# Mono_main_board_V3.net
KiCad netlist of a schematic drawn in EAGLE
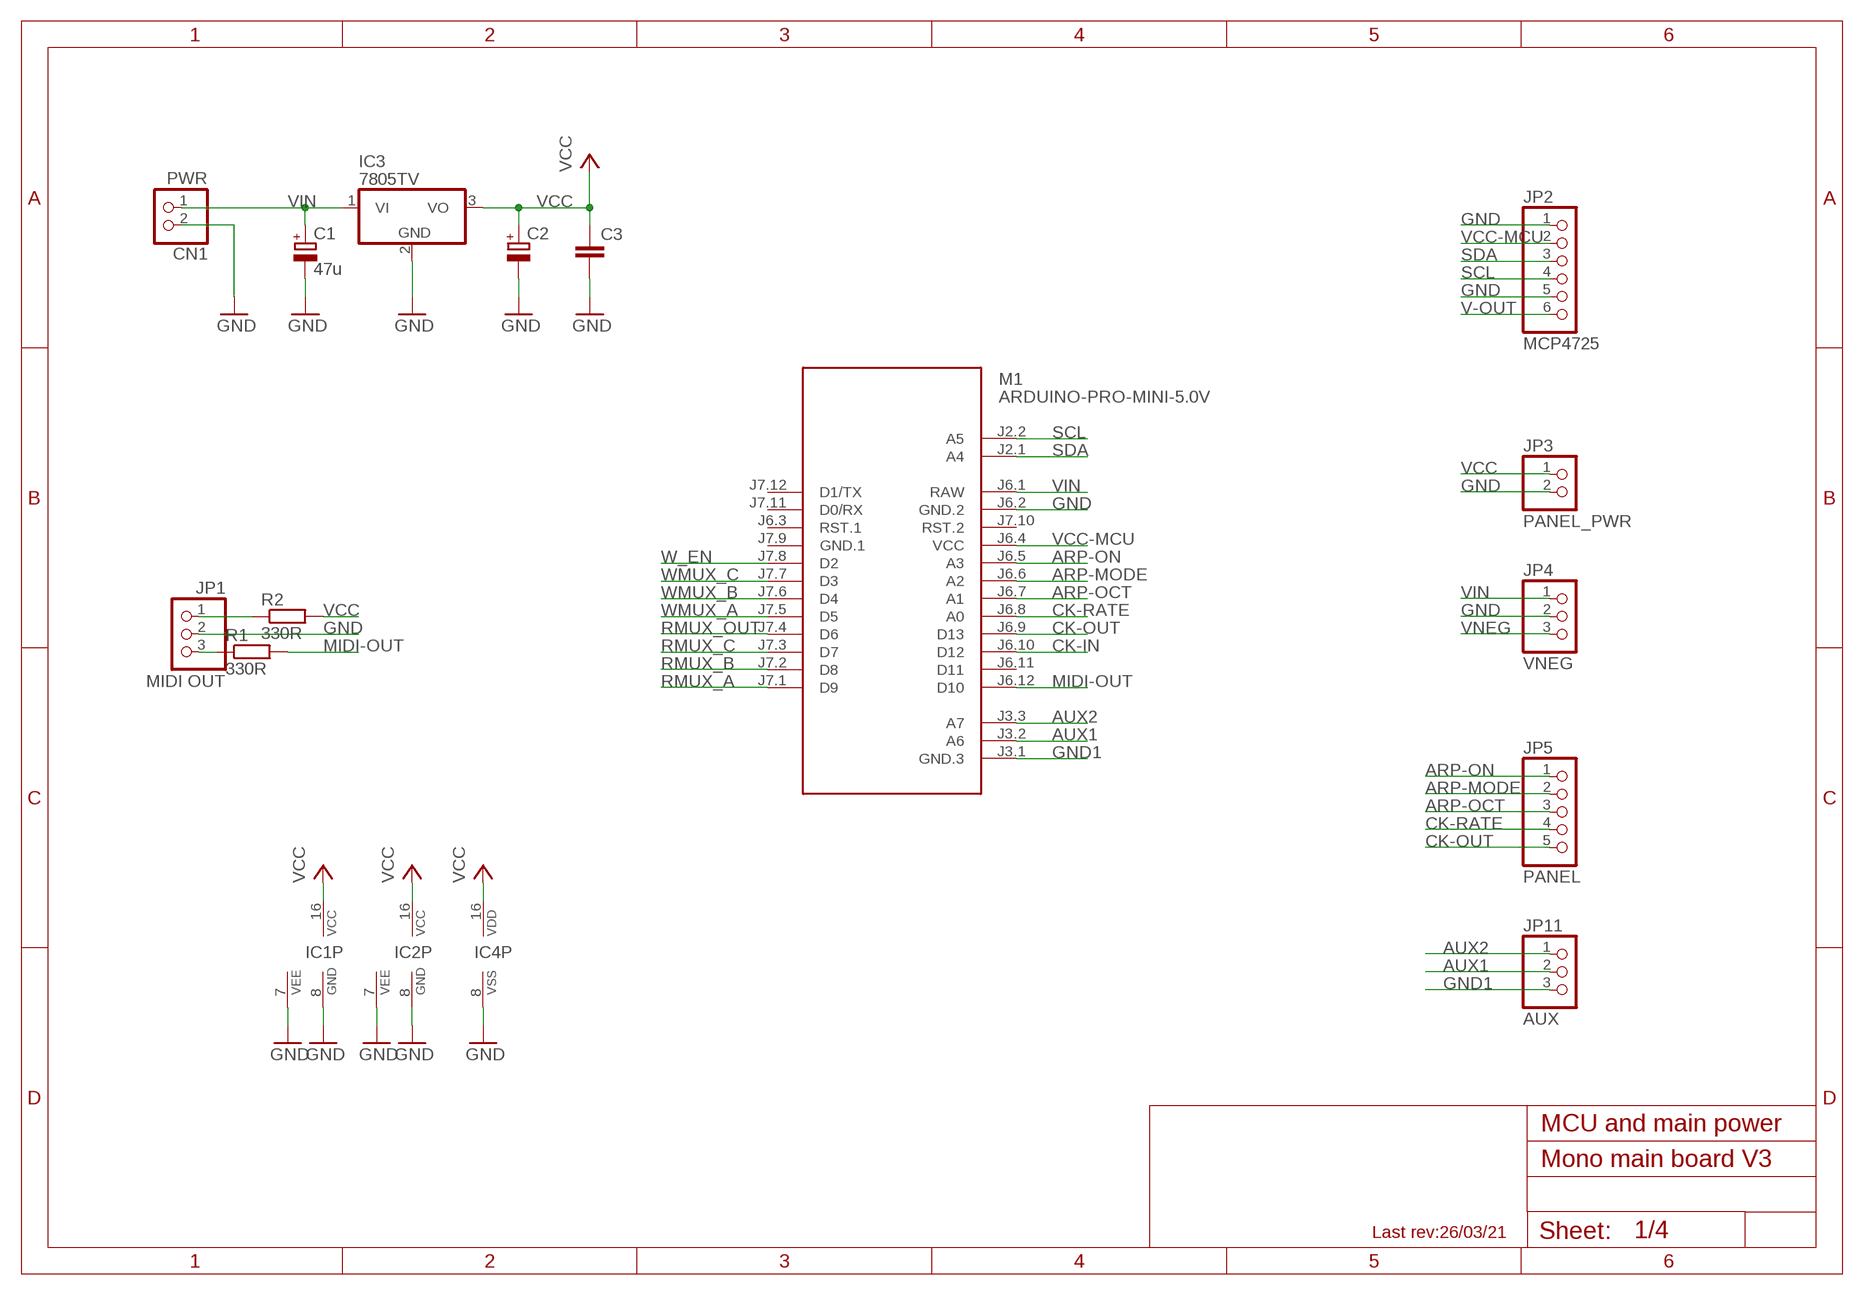
[diagram p0: schematic, sheet 1]
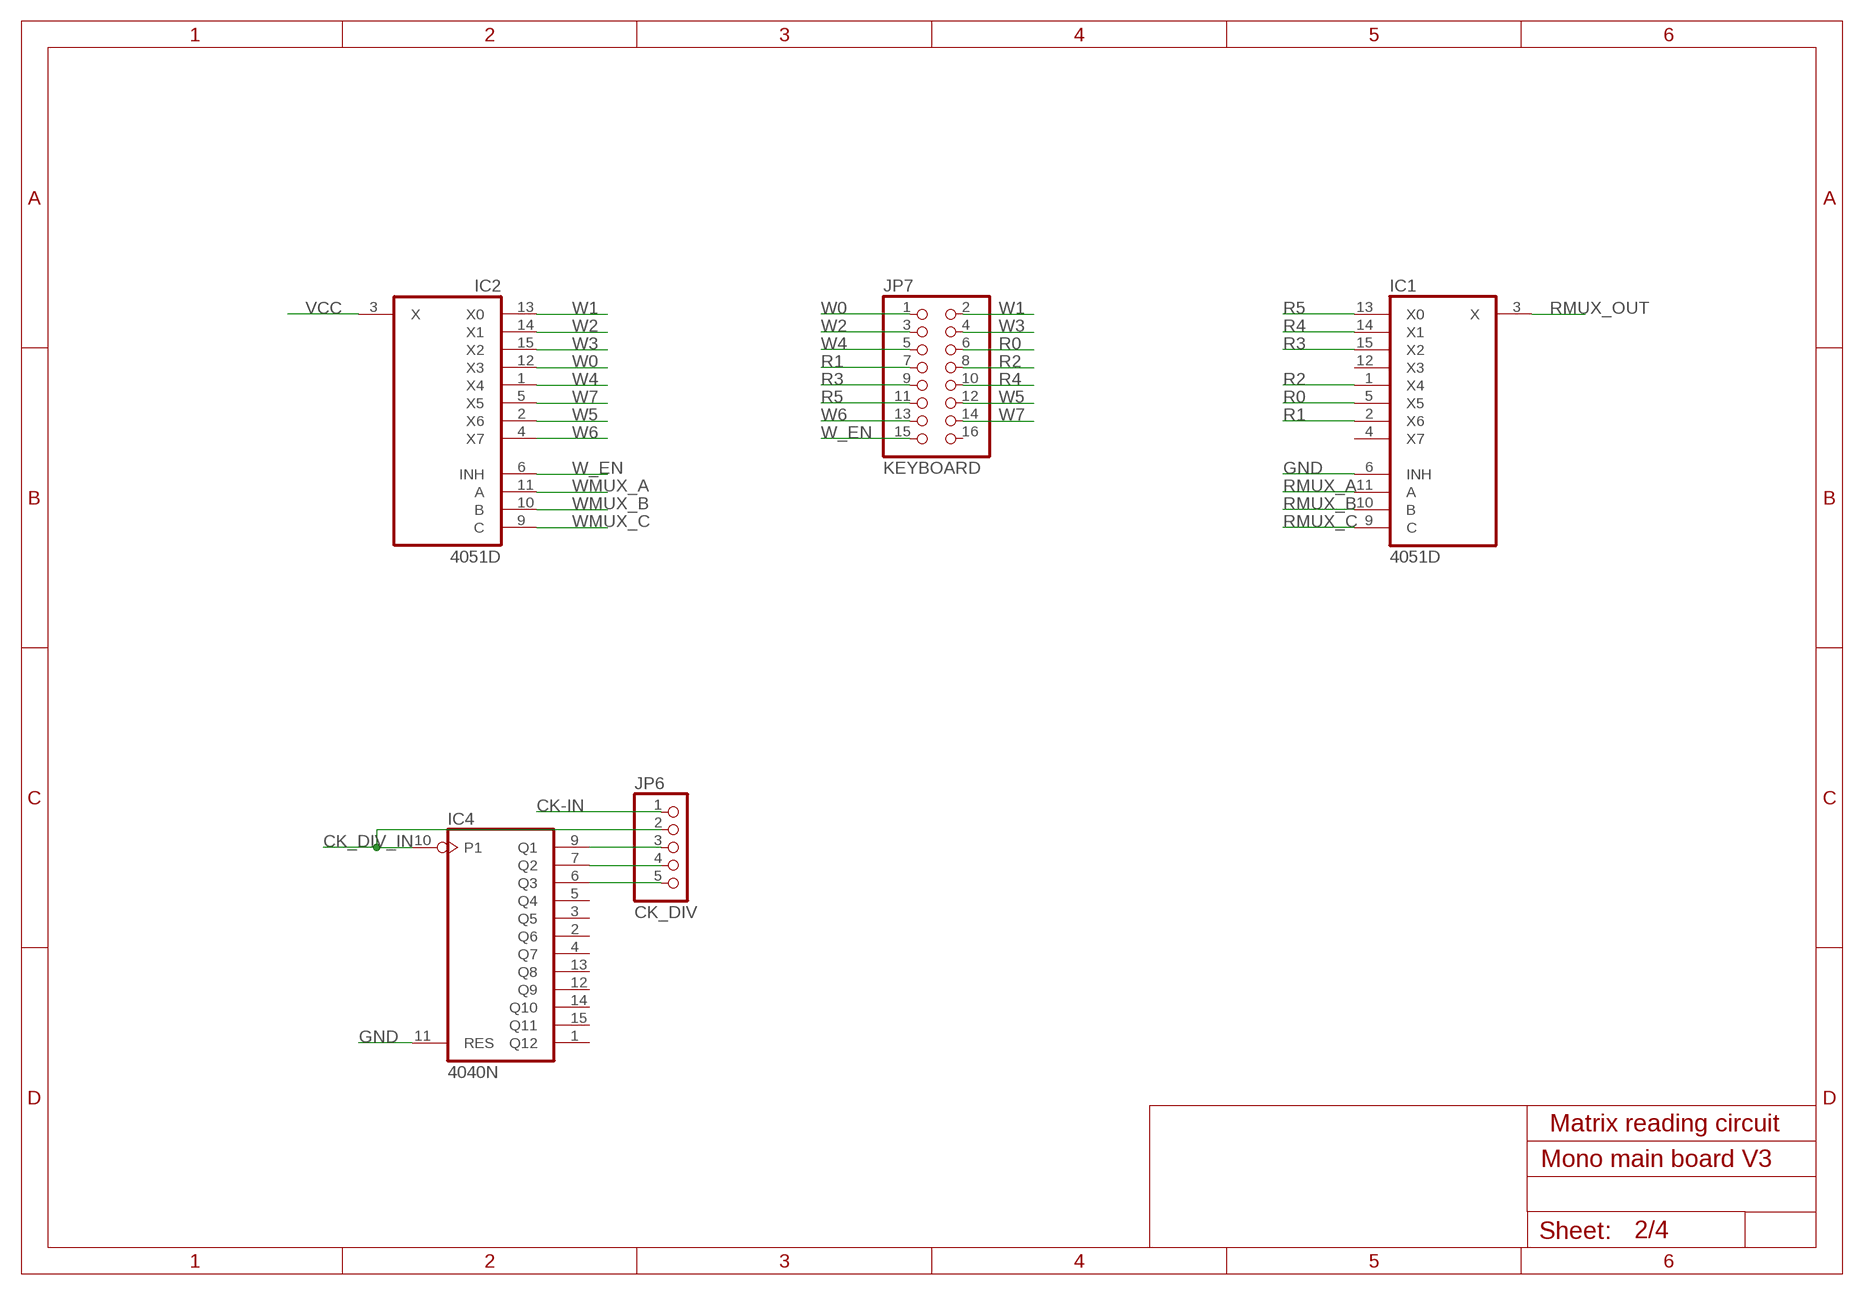
[diagram p1: schematic, sheet 2]
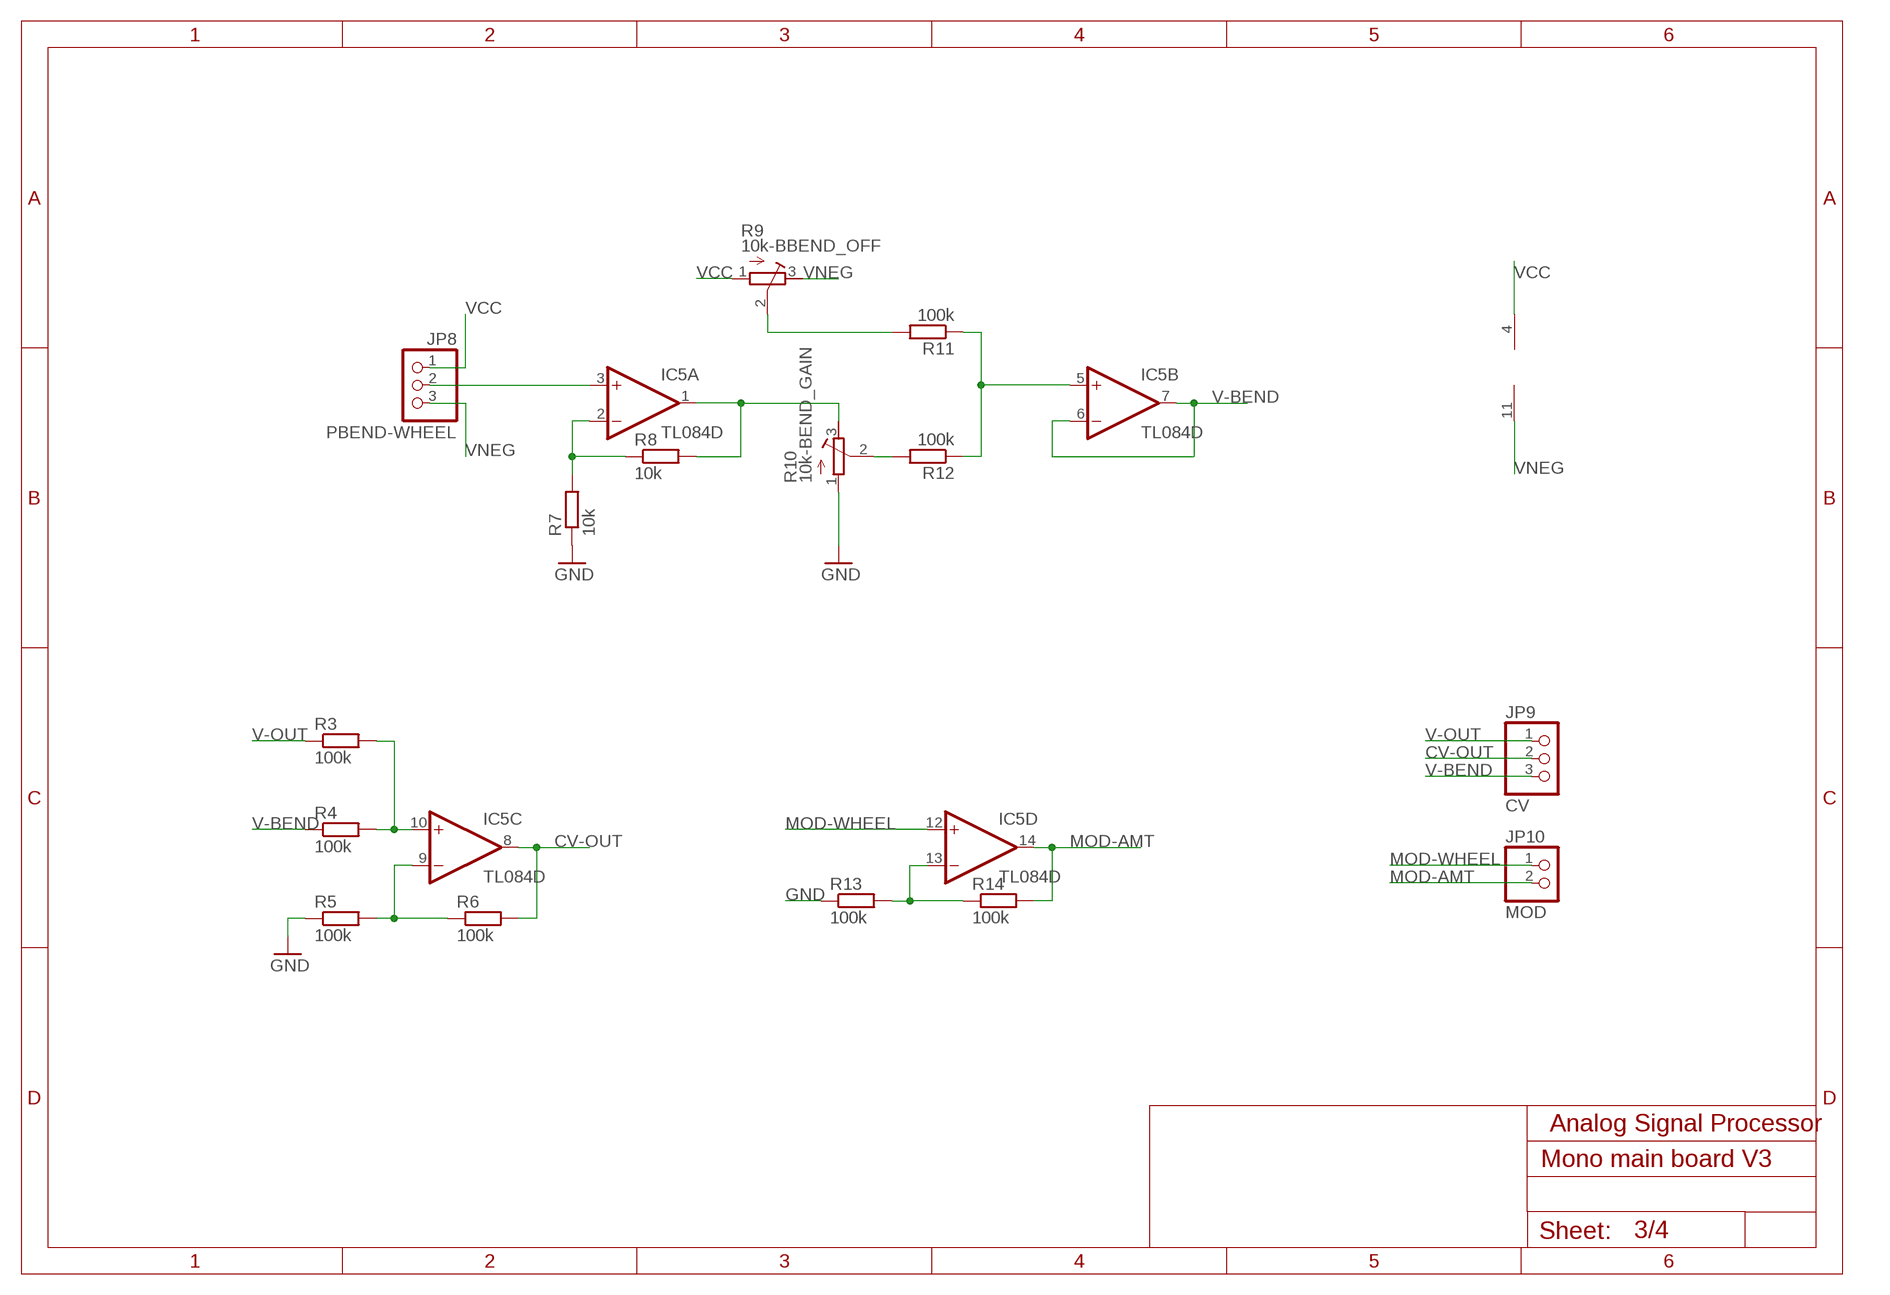
[diagram p2: schematic, sheet 3]
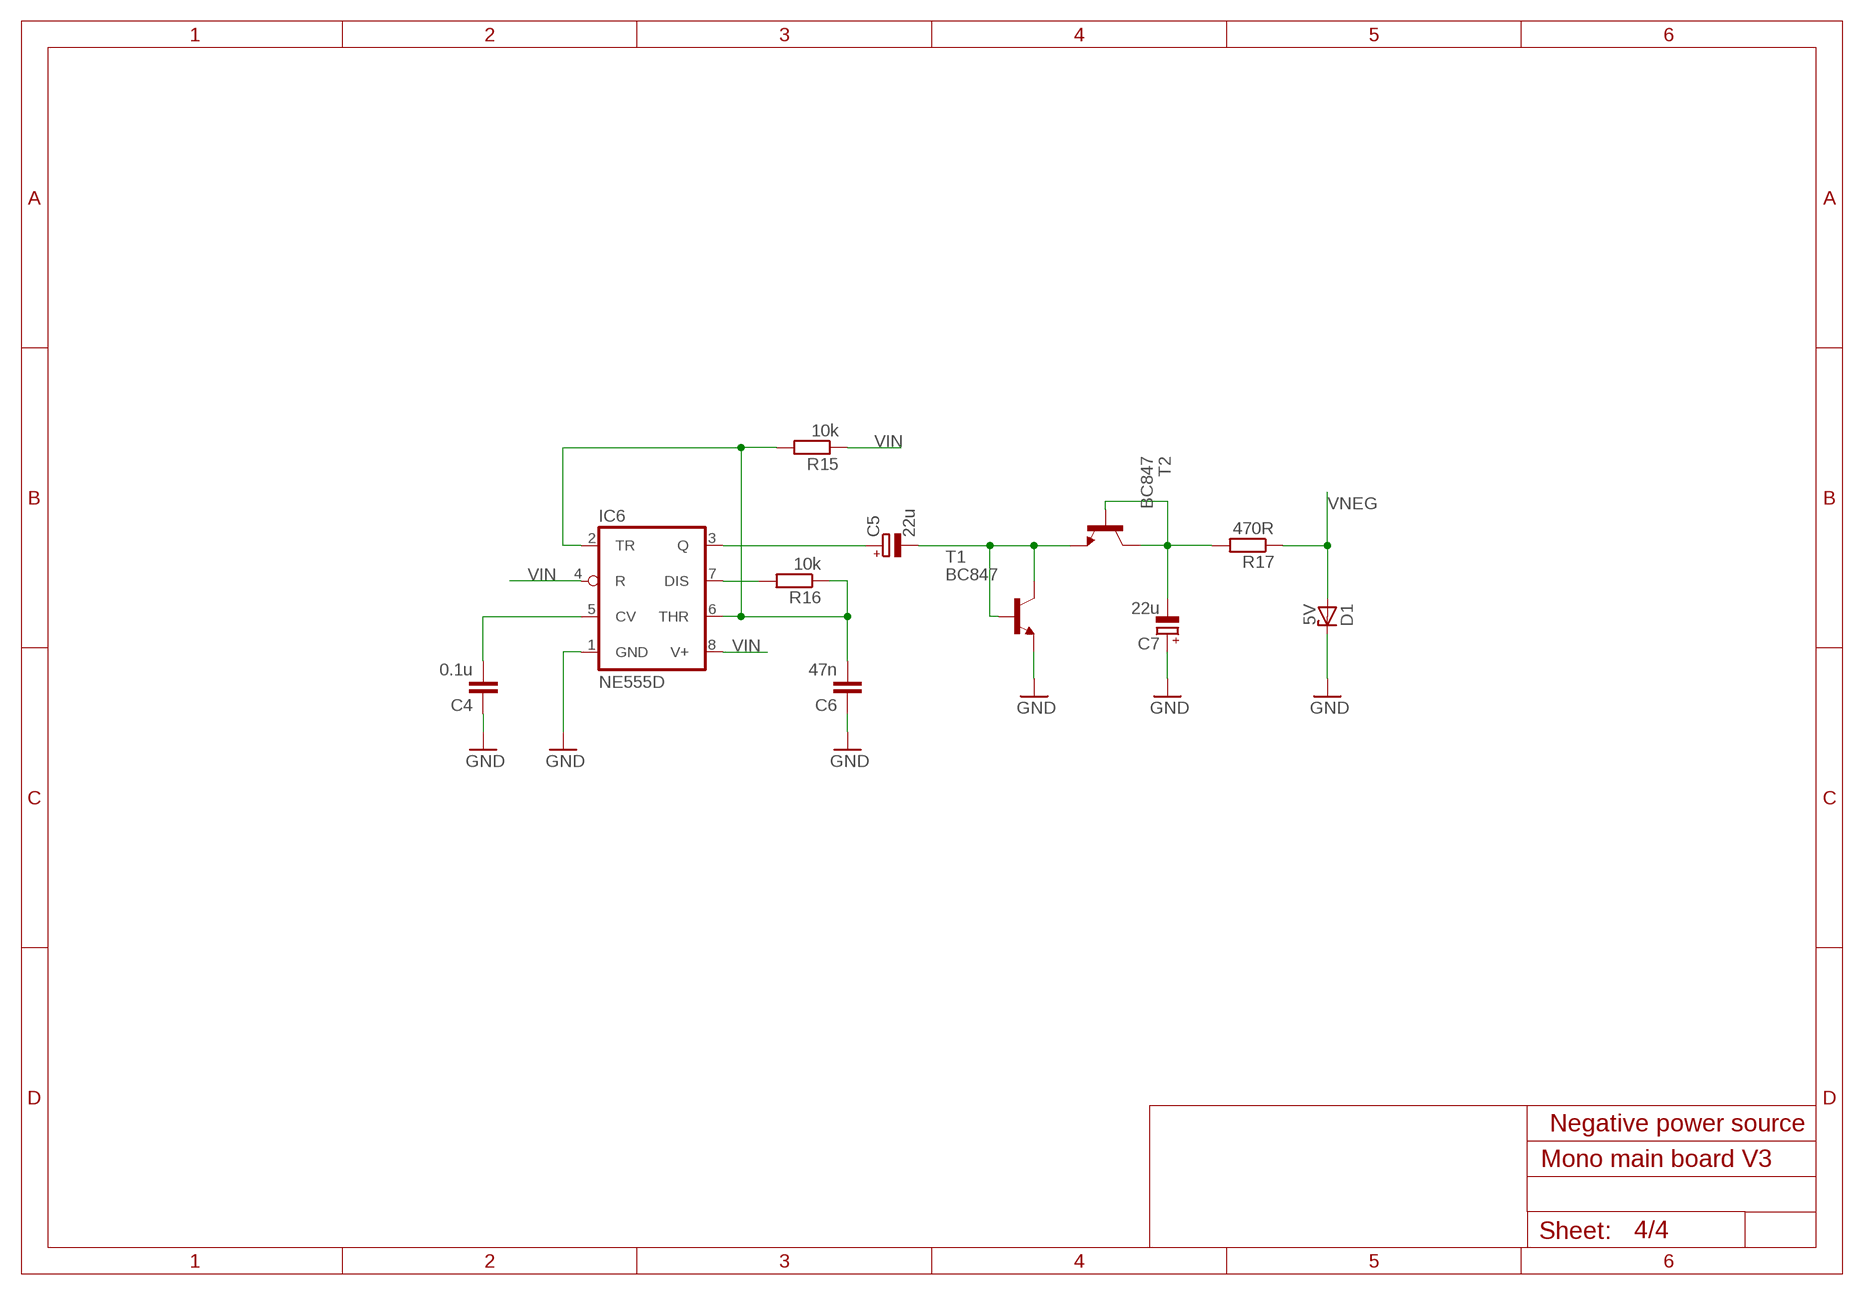
[diagram p3: schematic, sheet 4]

(export (version "E")
  (design (tool "Eeschema 10.0.6"))
  (components
    (comp (ref "IC5")
      (value "TL084D")
      (footprint "eagle-import:SO14")
      (libsource (lib "eagle-import") (part "TL084D"))
    )
    (comp (ref "JP8")
      (value "PBEND-WHEEL")
      (footprint "eagle-import:1X03")
      (libsource (lib "eagle-import") (part "PINHD-1X3"))
    )
    (comp (ref "JP9")
      (value "CV")
      (footprint "eagle-import:1X03")
      (libsource (lib "eagle-import") (part "PINHD-1X3"))
    )
    (comp (ref "JP10")
      (value "MOD")
      (footprint "eagle-import:1X02")
      (libsource (lib "eagle-import") (part "PINHD-1X2"))
    )
    (comp (ref "R3")
      (value "100k")
      (footprint "eagle-import:R0805")
      (libsource (lib "eagle-import") (part "R-EU_R0805"))
    )
    (comp (ref "R4")
      (value "100k")
      (footprint "eagle-import:R0805")
      (libsource (lib "eagle-import") (part "R-EU_R0805"))
    )
    (comp (ref "R5")
      (value "100k")
      (footprint "eagle-import:R0805")
      (libsource (lib "eagle-import") (part "R-EU_R0805"))
    )
    (comp (ref "R6")
      (value "100k")
      (footprint "eagle-import:R0805")
      (libsource (lib "eagle-import") (part "R-EU_R0805"))
    )
    (comp (ref "R7")
      (value "10k")
      (footprint "eagle-import:R0805")
      (libsource (lib "eagle-import") (part "R-EU_R0805"))
    )
    (comp (ref "R8")
      (value "10k")
      (footprint "eagle-import:R0805")
      (libsource (lib "eagle-import") (part "R-EU_R0805"))
    )
    (comp (ref "R9")
      (value "10k-BBEND_OFF")
      (footprint "eagle-import:RTRIM64W")
      (libsource (lib "eagle-import") (part "R-TRIMM64W"))
    )
    (comp (ref "R10")
      (value "10k-BEND_GAIN")
      (footprint "eagle-import:RTRIM64W")
      (libsource (lib "eagle-import") (part "R-TRIMM64W"))
    )
    (comp (ref "R11")
      (value "100k")
      (footprint "eagle-import:R0805")
      (libsource (lib "eagle-import") (part "R-EU_R0805"))
    )
    (comp (ref "R12")
      (value "100k")
      (footprint "eagle-import:R0805")
      (libsource (lib "eagle-import") (part "R-EU_R0805"))
    )
    (comp (ref "R13")
      (value "100k")
      (footprint "eagle-import:R0805")
      (libsource (lib "eagle-import") (part "R-EU_R0805"))
    )
    (comp (ref "R14")
      (value "100k")
      (footprint "eagle-import:R0805")
      (libsource (lib "eagle-import") (part "R-EU_R0805"))
    )
    (comp (ref "C1")
      (value "47u")
      (footprint "eagle-import:E5-8,5")
      (libsource (lib "eagle-import") (part "CPOL-EUE5-8.5"))
    )
    (comp (ref "C2")
      (value "CPOL-EUE5-8.5")
      (footprint "eagle-import:E5-8,5")
      (libsource (lib "eagle-import") (part "CPOL-EUE5-8.5"))
    )
    (comp (ref "C3")
      (value "C-EU050-025X075")
      (footprint "eagle-import:C050-025X075")
      (libsource (lib "eagle-import") (part "C-EU050-025X075"))
    )
    (comp (ref "CN1")
      (value "PWR")
      (footprint "eagle-import:JST-PH-2-THM")
      (libsource (lib "eagle-import") (part "JST_2PIN-THM"))
    )
    (comp (ref "IC1")
      (value "4051D")
      (footprint "eagle-import:SO16")
      (libsource (lib "eagle-import") (part "4051D"))
    )
    (comp (ref "IC2")
      (value "4051D")
      (footprint "eagle-import:SO16")
      (libsource (lib "eagle-import") (part "4051D"))
    )
    (comp (ref "IC3")
      (value "7805TV")
      (footprint "eagle-import:TO220V")
      (libsource (lib "eagle-import") (part "78TV05"))
    )
    (comp (ref "IC4")
      (value "4040N")
      (footprint "eagle-import:DIL16")
      (libsource (lib "eagle-import") (part "4040N"))
    )
    (comp (ref "JP1")
      (value "MIDI OUT")
      (footprint "eagle-import:1X03")
      (libsource (lib "eagle-import") (part "PINHD-1X3"))
    )
    (comp (ref "JP2")
      (value "MCP4725")
      (footprint "eagle-import:1X06-CLEANBIG")
      (libsource (lib "eagle-import") (part "PINHD-1X6CB"))
    )
    (comp (ref "JP3")
      (value "PANEL_PWR")
      (footprint "eagle-import:1X02")
      (libsource (lib "eagle-import") (part "PINHD-1X2"))
    )
    (comp (ref "JP4")
      (value "VNEG")
      (footprint "eagle-import:1X03")
      (libsource (lib "eagle-import") (part "PINHD-1X3"))
    )
    (comp (ref "JP5")
      (value "PANEL")
      (footprint "eagle-import:1X05")
      (libsource (lib "eagle-import") (part "PINHD-1X5"))
    )
    (comp (ref "JP11")
      (value "AUX")
      (footprint "eagle-import:1X03")
      (libsource (lib "eagle-import") (part "PINHD-1X3"))
    )
    (comp (ref "M1")
      (value "ARDUINO-PRO-MINI-5.0V")
      (footprint "eagle-import:ARDUINO-PRO-MINI#NP")
      (libsource (lib "eagle-import") (part "ARDUINO-PRO-MINI-#NP5.0V"))
    )
    (comp (ref "R1")
      (value "330R")
      (footprint "eagle-import:R0805")
      (libsource (lib "eagle-import") (part "R-EU_R0805"))
    )
    (comp (ref "R2")
      (value "330R")
      (footprint "eagle-import:R0805")
      (libsource (lib "eagle-import") (part "R-EU_R0805"))
    )
    (comp (ref "C4")
      (value "0.1u")
      (footprint "eagle-import:C0805")
      (libsource (lib "eagle-import") (part "C-EUC0805"))
    )
    (comp (ref "C5")
      (value "22u")
      (footprint "eagle-import:E5-10,5")
      (libsource (lib "eagle-import") (part "CPOL-EUE5-10.5"))
    )
    (comp (ref "C6")
      (value "47n")
      (footprint "eagle-import:C0805")
      (libsource (lib "eagle-import") (part "C-EUC0805"))
    )
    (comp (ref "C7")
      (value "22u")
      (footprint "eagle-import:E5-10,5")
      (libsource (lib "eagle-import") (part "CPOL-EUE5-10.5"))
    )
    (comp (ref "D1")
      (value "5V")
      (footprint "eagle-import:ZDIO-2.5")
      (libsource (lib "eagle-import") (part "ZENER-DIODEZD-2.5"))
    )
    (comp (ref "IC6")
      (value "NE555D")
      (footprint "eagle-import:SO08")
      (libsource (lib "eagle-import") (part "555DNE"))
    )
    (comp (ref "R15")
      (value "10k")
      (footprint "eagle-import:M0805")
      (libsource (lib "eagle-import") (part "R-EU_M0805"))
    )
    (comp (ref "R16")
      (value "10k")
      (footprint "eagle-import:M0805")
      (libsource (lib "eagle-import") (part "R-EU_M0805"))
    )
    (comp (ref "R17")
      (value "470R")
      (footprint "eagle-import:M0805")
      (libsource (lib "eagle-import") (part "R-EU_M0805"))
    )
    (comp (ref "T1")
      (value "BC847")
      (footprint "eagle-import:SOT23")
      (libsource (lib "eagle-import") (part "BC847"))
    )
    (comp (ref "T2")
      (value "BC847")
      (footprint "eagle-import:SOT23")
      (libsource (lib "eagle-import") (part "BC847"))
    )
    (comp (ref "JP6")
      (value "CK_DIV")
      (footprint "eagle-import:1X05")
      (libsource (lib "eagle-import") (part "PINHD-1X5"))
    )
    (comp (ref "JP7")
      (value "KEYBOARD")
      (footprint "eagle-import:2X08")
      (libsource (lib "eagle-import") (part "PINHD-2X8"))
    )
  )
  (nets
    (net (code "1") (name "ARP-MODE") (class "Default")
      (node (ref "JP5") (pin "2") (pinfunction "2_2") (pintype "passive"))
      (node (ref "M1") (pin "J6.6") (pinfunction "A2_J6.6") (pintype "bidirectional"))
    )
    (net (code "2") (name "ARP-OCT") (class "Default")
      (node (ref "JP5") (pin "3") (pinfunction "3_3") (pintype "passive"))
      (node (ref "M1") (pin "J6.7") (pinfunction "A1_J6.7") (pintype "bidirectional"))
    )
    (net (code "3") (name "ARP-ON") (class "Default")
      (node (ref "JP5") (pin "1") (pinfunction "1_1") (pintype "passive"))
      (node (ref "M1") (pin "J6.5") (pinfunction "A3_J6.5") (pintype "bidirectional"))
    )
    (net (code "4") (name "AUX1") (class "Default")
      (node (ref "JP11") (pin "2") (pinfunction "2_2") (pintype "passive"))
      (node (ref "M1") (pin "J3.2") (pinfunction "A6_J3.2") (pintype "bidirectional"))
    )
    (net (code "5") (name "AUX2") (class "Default")
      (node (ref "JP11") (pin "1") (pinfunction "1_1") (pintype "passive"))
      (node (ref "M1") (pin "J3.3") (pinfunction "A7_J3.3") (pintype "bidirectional"))
    )
    (net (code "6") (name "CK-IN") (class "Default")
      (node (ref "JP6") (pin "1") (pinfunction "1_1") (pintype "passive"))
      (node (ref "M1") (pin "J6.10") (pinfunction "D12_J6.10") (pintype "bidirectional"))
    )
    (net (code "7") (name "CK-OUT") (class "Default")
      (node (ref "JP5") (pin "5") (pinfunction "5_5") (pintype "passive"))
      (node (ref "M1") (pin "J6.9") (pinfunction "D13_J6.9") (pintype "bidirectional"))
    )
    (net (code "8") (name "CK-RATE") (class "Default")
      (node (ref "JP5") (pin "4") (pinfunction "4_4") (pintype "passive"))
      (node (ref "M1") (pin "J6.8") (pinfunction "A0_J6.8") (pintype "bidirectional"))
    )
    (net (code "9") (name "CK_DIV_IN") (class "Default")
      (node (ref "IC4") (pin "10") (pinfunction "P1_10") (pintype "input"))
      (node (ref "JP6") (pin "2") (pinfunction "2_2") (pintype "passive"))
    )
    (net (code "10") (name "CV-OUT") (class "Default")
      (node (ref "IC5") (pin "8") (pinfunction "OUT_8") (pintype "output"))
      (node (ref "JP9") (pin "2") (pinfunction "2_2") (pintype "passive"))
      (node (ref "R6") (pin "2") (pinfunction "2_2") (pintype "passive"))
    )
    (net (code "11") (name "GND") (class "Default")
      (node (ref "C1") (pin "-") (pinfunction "-_-") (pintype "passive"))
      (node (ref "C2") (pin "-") (pinfunction "-_-") (pintype "passive"))
      (node (ref "C3") (pin "2") (pinfunction "2_2") (pintype "passive"))
      (node (ref "C4") (pin "1") (pinfunction "1_1") (pintype "passive"))
      (node (ref "C6") (pin "1") (pinfunction "1_1") (pintype "passive"))
      (node (ref "C7") (pin "+") (pinfunction "+_+") (pintype "passive"))
      (node (ref "CN1") (pin "2") (pinfunction "1_2") (pintype "passive"))
      (node (ref "D1") (pin "C") (pinfunction "C_C") (pintype "passive"))
      (node (ref "IC1") (pin "6") (pinfunction "INH_6") (pintype "input"))
      (node (ref "IC1") (pin "7") (pinfunction "VEE_7") (pintype "power_in"))
      (node (ref "IC1") (pin "8") (pinfunction "GND_8") (pintype "power_in"))
      (node (ref "IC2") (pin "7") (pinfunction "VEE_7") (pintype "power_in"))
      (node (ref "IC2") (pin "8") (pinfunction "GND_8") (pintype "power_in"))
      (node (ref "IC3") (pin "2") (pinfunction "GND_2") (pintype "passive"))
      (node (ref "IC4") (pin "11") (pinfunction "RES_11") (pintype "input"))
      (node (ref "IC4") (pin "8") (pinfunction "VSS_8") (pintype "power_in"))
      (node (ref "IC6") (pin "1") (pinfunction "GND_1") (pintype "power_in"))
      (node (ref "JP1") (pin "2") (pinfunction "2_2") (pintype "passive"))
      (node (ref "JP2") (pin "1") (pinfunction "1_1") (pintype "passive"))
      (node (ref "JP2") (pin "5") (pinfunction "5_5") (pintype "passive"))
      (node (ref "JP3") (pin "2") (pinfunction "2_2") (pintype "passive"))
      (node (ref "JP4") (pin "2") (pinfunction "2_2") (pintype "passive"))
      (node (ref "M1") (pin "J6.2") (pinfunction "GND.2_J6.2") (pintype "power_in"))
      (node (ref "R10") (pin "1") (pinfunction "A_1") (pintype "passive"))
      (node (ref "R13") (pin "1") (pinfunction "1_1") (pintype "passive"))
      (node (ref "R5") (pin "1") (pinfunction "1_1") (pintype "passive"))
      (node (ref "R7") (pin "1") (pinfunction "1_1") (pintype "passive"))
      (node (ref "T1") (pin "2") (pinfunction "E_2") (pintype "passive"))
    )
    (net (code "12") (name "GND.1") (class "Default")
      (node (ref "M1") (pin "J7.9") (pinfunction "GND.1_J7.9") (pintype "power_in"))
    )
    (net (code "13") (name "GND1") (class "Default")
      (node (ref "JP11") (pin "3") (pinfunction "3_3") (pintype "passive"))
      (node (ref "M1") (pin "J3.1") (pinfunction "GND.3_J3.1") (pintype "bidirectional"))
    )
    (net (code "14") (name "MIDI-OUT") (class "Default")
      (node (ref "M1") (pin "J6.12") (pinfunction "D10_J6.12") (pintype "bidirectional"))
      (node (ref "R1") (pin "2") (pinfunction "2_2") (pintype "passive"))
    )
    (net (code "15") (name "MOD-AMT") (class "Default")
      (node (ref "IC5") (pin "14") (pinfunction "OUT_14") (pintype "output"))
      (node (ref "JP10") (pin "2") (pinfunction "2_2") (pintype "passive"))
      (node (ref "R14") (pin "2") (pinfunction "2_2") (pintype "passive"))
    )
    (net (code "16") (name "MOD-WHEEL") (class "Default")
      (node (ref "IC5") (pin "12") (pinfunction "+IN_12") (pintype "input"))
      (node (ref "JP10") (pin "1") (pinfunction "1_1") (pintype "passive"))
    )
    (net (code "17") (name "Net-(IC4A-Q1)") (class "Default")
      (node (ref "IC4") (pin "9") (pinfunction "Q1_9") (pintype "output"))
      (node (ref "JP6") (pin "3") (pinfunction "3_3") (pintype "passive"))
    )
    (net (code "18") (name "Net-(IC4A-Q2)") (class "Default")
      (node (ref "IC4") (pin "7") (pinfunction "Q2_7") (pintype "output"))
      (node (ref "JP6") (pin "4") (pinfunction "4_4") (pintype "passive"))
    )
    (net (code "19") (name "Net-(IC4A-Q3)") (class "Default")
      (node (ref "IC4") (pin "6") (pinfunction "Q3_6") (pintype "output"))
      (node (ref "JP6") (pin "5") (pinfunction "5_5") (pintype "passive"))
    )
    (net (code "20") (name "Net-(IC5A-+IN)") (class "Default")
      (node (ref "IC5") (pin "3") (pinfunction "+IN_3") (pintype "input"))
      (node (ref "JP8") (pin "2") (pinfunction "2_2") (pintype "passive"))
    )
    (net (code "21") (name "Net-(IC5A--IN)") (class "Default")
      (node (ref "IC5") (pin "2") (pinfunction "-IN_2") (pintype "input"))
      (node (ref "R7") (pin "2") (pinfunction "2_2") (pintype "passive"))
      (node (ref "R8") (pin "1") (pinfunction "1_1") (pintype "passive"))
    )
    (net (code "22") (name "Net-(IC5A-OUT)") (class "Default")
      (node (ref "IC5") (pin "1") (pinfunction "OUT_1") (pintype "output"))
      (node (ref "R10") (pin "3") (pinfunction "E_3") (pintype "passive"))
      (node (ref "R8") (pin "2") (pinfunction "2_2") (pintype "passive"))
    )
    (net (code "23") (name "Net-(IC5B-+IN)") (class "Default")
      (node (ref "IC5") (pin "5") (pinfunction "+IN_5") (pintype "input"))
      (node (ref "R11") (pin "1") (pinfunction "1_1") (pintype "passive"))
      (node (ref "R12") (pin "1") (pinfunction "1_1") (pintype "passive"))
    )
    (net (code "24") (name "Net-(IC5C-+IN)") (class "Default")
      (node (ref "IC5") (pin "10") (pinfunction "+IN_10") (pintype "input"))
      (node (ref "R3") (pin "2") (pinfunction "2_2") (pintype "passive"))
      (node (ref "R4") (pin "2") (pinfunction "2_2") (pintype "passive"))
    )
    (net (code "25") (name "Net-(IC5C--IN)") (class "Default")
      (node (ref "IC5") (pin "9") (pinfunction "-IN_9") (pintype "input"))
      (node (ref "R5") (pin "2") (pinfunction "2_2") (pintype "passive"))
      (node (ref "R6") (pin "1") (pinfunction "1_1") (pintype "passive"))
    )
    (net (code "26") (name "Net-(IC5D--IN)") (class "Default")
      (node (ref "IC5") (pin "13") (pinfunction "-IN_13") (pintype "input"))
      (node (ref "R13") (pin "2") (pinfunction "2_2") (pintype "passive"))
      (node (ref "R14") (pin "1") (pinfunction "1_1") (pintype "passive"))
    )
    (net (code "27") (name "Net-(IC6-CV)") (class "Default")
      (node (ref "C4") (pin "2") (pinfunction "2_2") (pintype "passive"))
      (node (ref "IC6") (pin "5") (pinfunction "CV_5") (pintype "input"))
    )
    (net (code "28") (name "Net-(IC6-DIS)") (class "Default")
      (node (ref "IC6") (pin "7") (pinfunction "DIS_7") (pintype "input"))
      (node (ref "R16") (pin "2") (pinfunction "2_2") (pintype "passive"))
    )
    (net (code "29") (name "Net-(IC6-Q)") (class "Default")
      (node (ref "C5") (pin "+") (pinfunction "+_+") (pintype "passive"))
      (node (ref "IC6") (pin "3") (pinfunction "Q_3") (pintype "output"))
    )
    (net (code "30") (name "Net-(IC6-THR)") (class "Default")
      (node (ref "C6") (pin "2") (pinfunction "2_2") (pintype "passive"))
      (node (ref "IC6") (pin "2") (pinfunction "TR_2") (pintype "input"))
      (node (ref "IC6") (pin "6") (pinfunction "THR_6") (pintype "input"))
      (node (ref "R15") (pin "2") (pinfunction "2_2") (pintype "passive"))
      (node (ref "R16") (pin "1") (pinfunction "1_1") (pintype "passive"))
    )
    (net (code "31") (name "Net-(JP1-Pad1)") (class "Default")
      (node (ref "JP1") (pin "1") (pinfunction "1_1") (pintype "passive"))
      (node (ref "R2") (pin "1") (pinfunction "1_1") (pintype "passive"))
    )
    (net (code "32") (name "Net-(JP1-Pad3)") (class "Default")
      (node (ref "JP1") (pin "3") (pinfunction "3_3") (pintype "passive"))
      (node (ref "R1") (pin "1") (pinfunction "1_1") (pintype "passive"))
    )
    (net (code "33") (name "Net-(R9-S)") (class "Default")
      (node (ref "R11") (pin "2") (pinfunction "2_2") (pintype "passive"))
      (node (ref "R9") (pin "2") (pinfunction "S_2") (pintype "passive"))
    )
    (net (code "34") (name "Net-(R10-S)") (class "Default")
      (node (ref "R10") (pin "2") (pinfunction "S_2") (pintype "passive"))
      (node (ref "R12") (pin "2") (pinfunction "2_2") (pintype "passive"))
    )
    (net (code "35") (name "Net-(T1-B)") (class "Default")
      (node (ref "C5") (pin "-") (pinfunction "-_-") (pintype "passive"))
      (node (ref "T1") (pin "1") (pinfunction "B_1") (pintype "passive"))
      (node (ref "T1") (pin "3") (pinfunction "C_3") (pintype "passive"))
      (node (ref "T2") (pin "2") (pinfunction "E_2") (pintype "passive"))
    )
    (net (code "36") (name "Net-(T2-B)") (class "Default")
      (node (ref "C7") (pin "-") (pinfunction "-_-") (pintype "passive"))
      (node (ref "R17") (pin "2") (pinfunction "2_2") (pintype "passive"))
      (node (ref "T2") (pin "1") (pinfunction "B_1") (pintype "passive"))
      (node (ref "T2") (pin "3") (pinfunction "C_3") (pintype "passive"))
    )
    (net (code "37") (name "R0") (class "Default")
      (node (ref "IC1") (pin "5") (pinfunction "X5_5") (pintype "bidirectional"))
      (node (ref "JP7") (pin "6") (pinfunction "6_6") (pintype "passive"))
    )
    (net (code "38") (name "R1") (class "Default")
      (node (ref "IC1") (pin "2") (pinfunction "X6_2") (pintype "bidirectional"))
      (node (ref "JP7") (pin "7") (pinfunction "7_7") (pintype "passive"))
    )
    (net (code "39") (name "R2") (class "Default")
      (node (ref "IC1") (pin "1") (pinfunction "X4_1") (pintype "bidirectional"))
      (node (ref "JP7") (pin "8") (pinfunction "8_8") (pintype "passive"))
    )
    (net (code "40") (name "R3") (class "Default")
      (node (ref "IC1") (pin "15") (pinfunction "X2_15") (pintype "bidirectional"))
      (node (ref "JP7") (pin "9") (pinfunction "9_9") (pintype "passive"))
    )
    (net (code "41") (name "R4") (class "Default")
      (node (ref "IC1") (pin "14") (pinfunction "X1_14") (pintype "bidirectional"))
      (node (ref "JP7") (pin "10") (pinfunction "10_10") (pintype "passive"))
    )
    (net (code "42") (name "R5") (class "Default")
      (node (ref "IC1") (pin "13") (pinfunction "X0_13") (pintype "bidirectional"))
      (node (ref "JP7") (pin "11") (pinfunction "11_11") (pintype "passive"))
    )
    (net (code "43") (name "RMUX_A") (class "Default")
      (node (ref "IC1") (pin "11") (pinfunction "A_11") (pintype "input"))
      (node (ref "M1") (pin "J7.1") (pinfunction "D9_J7.1") (pintype "bidirectional"))
    )
    (net (code "44") (name "RMUX_B") (class "Default")
      (node (ref "IC1") (pin "10") (pinfunction "B_10") (pintype "input"))
      (node (ref "M1") (pin "J7.2") (pinfunction "D8_J7.2") (pintype "bidirectional"))
    )
    (net (code "45") (name "RMUX_C") (class "Default")
      (node (ref "IC1") (pin "9") (pinfunction "C_9") (pintype "input"))
      (node (ref "M1") (pin "J7.3") (pinfunction "D7_J7.3") (pintype "bidirectional"))
    )
    (net (code "46") (name "RMUX_OUT") (class "Default")
      (node (ref "IC1") (pin "3") (pinfunction "X_3") (pintype "bidirectional"))
      (node (ref "M1") (pin "J7.4") (pinfunction "D6_J7.4") (pintype "bidirectional"))
    )
    (net (code "47") (name "SCL") (class "Default")
      (node (ref "JP2") (pin "4") (pinfunction "4_4") (pintype "passive"))
      (node (ref "M1") (pin "J2.2") (pinfunction "A5_J2.2") (pintype "bidirectional"))
    )
    (net (code "48") (name "SDA") (class "Default")
      (node (ref "JP2") (pin "3") (pinfunction "3_3") (pintype "passive"))
      (node (ref "M1") (pin "J2.1") (pinfunction "A4_J2.1") (pintype "bidirectional"))
    )
    (net (code "49") (name "V-BEND") (class "Default")
      (node (ref "IC5") (pin "6") (pinfunction "-IN_6") (pintype "input"))
      (node (ref "IC5") (pin "7") (pinfunction "OUT_7") (pintype "output"))
      (node (ref "JP9") (pin "3") (pinfunction "3_3") (pintype "passive"))
      (node (ref "R4") (pin "1") (pinfunction "1_1") (pintype "passive"))
    )
    (net (code "50") (name "V-OUT") (class "Default")
      (node (ref "JP2") (pin "6") (pinfunction "6_6") (pintype "passive"))
      (node (ref "JP9") (pin "1") (pinfunction "1_1") (pintype "passive"))
      (node (ref "R3") (pin "1") (pinfunction "1_1") (pintype "passive"))
    )
    (net (code "51") (name "VCC") (class "Default")
      (node (ref "C2") (pin "+") (pinfunction "+_+") (pintype "passive"))
      (node (ref "C3") (pin "1") (pinfunction "1_1") (pintype "passive"))
      (node (ref "IC1") (pin "16") (pinfunction "VCC_16") (pintype "power_in"))
      (node (ref "IC2") (pin "16") (pinfunction "VCC_16") (pintype "power_in"))
      (node (ref "IC2") (pin "3") (pinfunction "X_3") (pintype "bidirectional"))
      (node (ref "IC3") (pin "3") (pinfunction "VO_3") (pintype "passive"))
      (node (ref "IC4") (pin "16") (pinfunction "VDD_16") (pintype "power_in"))
      (node (ref "IC5") (pin "4") (pinfunction "V+_4") (pintype "power_in"))
      (node (ref "JP3") (pin "1") (pinfunction "1_1") (pintype "passive"))
      (node (ref "JP8") (pin "1") (pinfunction "1_1") (pintype "passive"))
      (node (ref "R2") (pin "2") (pinfunction "2_2") (pintype "passive"))
      (node (ref "R9") (pin "1") (pinfunction "A_1") (pintype "passive"))
    )
    (net (code "52") (name "VCC-MCU") (class "Default")
      (node (ref "JP2") (pin "2") (pinfunction "2_2") (pintype "passive"))
      (node (ref "M1") (pin "J6.4") (pinfunction "VCC_J6.4") (pintype "power_in"))
    )
    (net (code "53") (name "VIN") (class "Default")
      (node (ref "C1") (pin "+") (pinfunction "+_+") (pintype "passive"))
      (node (ref "CN1") (pin "1") (pinfunction "2_1") (pintype "passive"))
      (node (ref "IC3") (pin "1") (pinfunction "VI_1") (pintype "input"))
      (node (ref "IC6") (pin "4") (pinfunction "R_4") (pintype "input"))
      (node (ref "IC6") (pin "8") (pinfunction "V+_8") (pintype "power_in"))
      (node (ref "JP4") (pin "1") (pinfunction "1_1") (pintype "passive"))
      (node (ref "M1") (pin "J6.1") (pinfunction "RAW_J6.1") (pintype "power_in"))
      (node (ref "R15") (pin "1") (pinfunction "1_1") (pintype "passive"))
    )
    (net (code "54") (name "VNEG") (class "Default")
      (node (ref "D1") (pin "A") (pinfunction "A_A") (pintype "passive"))
      (node (ref "IC5") (pin "11") (pinfunction "V-_11") (pintype "power_in"))
      (node (ref "JP4") (pin "3") (pinfunction "3_3") (pintype "passive"))
      (node (ref "JP8") (pin "3") (pinfunction "3_3") (pintype "passive"))
      (node (ref "R17") (pin "1") (pinfunction "1_1") (pintype "passive"))
      (node (ref "R9") (pin "3") (pinfunction "E_3") (pintype "passive"))
    )
    (net (code "55") (name "W0") (class "Default")
      (node (ref "IC2") (pin "12") (pinfunction "X3_12") (pintype "bidirectional"))
      (node (ref "JP7") (pin "1") (pinfunction "1_1") (pintype "passive"))
    )
    (net (code "56") (name "W1") (class "Default")
      (node (ref "IC2") (pin "13") (pinfunction "X0_13") (pintype "bidirectional"))
      (node (ref "JP7") (pin "2") (pinfunction "2_2") (pintype "passive"))
    )
    (net (code "57") (name "W2") (class "Default")
      (node (ref "IC2") (pin "14") (pinfunction "X1_14") (pintype "bidirectional"))
      (node (ref "JP7") (pin "3") (pinfunction "3_3") (pintype "passive"))
    )
    (net (code "58") (name "W3") (class "Default")
      (node (ref "IC2") (pin "15") (pinfunction "X2_15") (pintype "bidirectional"))
      (node (ref "JP7") (pin "4") (pinfunction "4_4") (pintype "passive"))
    )
    (net (code "59") (name "W4") (class "Default")
      (node (ref "IC2") (pin "1") (pinfunction "X4_1") (pintype "bidirectional"))
      (node (ref "JP7") (pin "5") (pinfunction "5_5") (pintype "passive"))
    )
    (net (code "60") (name "W5") (class "Default")
      (node (ref "IC2") (pin "2") (pinfunction "X6_2") (pintype "bidirectional"))
      (node (ref "JP7") (pin "12") (pinfunction "12_12") (pintype "passive"))
    )
    (net (code "61") (name "W6") (class "Default")
      (node (ref "IC2") (pin "4") (pinfunction "X7_4") (pintype "bidirectional"))
      (node (ref "JP7") (pin "13") (pinfunction "13_13") (pintype "passive"))
    )
    (net (code "62") (name "W7") (class "Default")
      (node (ref "IC2") (pin "5") (pinfunction "X5_5") (pintype "bidirectional"))
      (node (ref "JP7") (pin "14") (pinfunction "14_14") (pintype "passive"))
    )
    (net (code "63") (name "WMUX_A") (class "Default")
      (node (ref "IC2") (pin "11") (pinfunction "A_11") (pintype "input"))
      (node (ref "M1") (pin "J7.5") (pinfunction "D5_J7.5") (pintype "bidirectional"))
    )
    (net (code "64") (name "WMUX_B") (class "Default")
      (node (ref "IC2") (pin "10") (pinfunction "B_10") (pintype "input"))
      (node (ref "M1") (pin "J7.6") (pinfunction "D4_J7.6") (pintype "bidirectional"))
    )
    (net (code "65") (name "WMUX_C") (class "Default")
      (node (ref "IC2") (pin "9") (pinfunction "C_9") (pintype "input"))
      (node (ref "M1") (pin "J7.7") (pinfunction "D3_J7.7") (pintype "bidirectional"))
    )
    (net (code "66") (name "W_EN") (class "Default")
      (node (ref "IC2") (pin "6") (pinfunction "INH_6") (pintype "input"))
      (node (ref "JP7") (pin "15") (pinfunction "15_15") (pintype "passive"))
      (node (ref "M1") (pin "J7.8") (pinfunction "D2_J7.8") (pintype "bidirectional"))
    )
    (net (code "67") (name "unconnected-(IC1A-X3-Pad12)") (class "Default")
      (node (ref "IC1") (pin "12") (pinfunction "X3_12") (pintype "bidirectional"))
    )
    (net (code "68") (name "unconnected-(IC1A-X7-Pad4)") (class "Default")
      (node (ref "IC1") (pin "4") (pinfunction "X7_4") (pintype "bidirectional"))
    )
    (net (code "69") (name "unconnected-(IC4A-Q4-Pad5)") (class "Default")
      (node (ref "IC4") (pin "5") (pinfunction "Q4_5") (pintype "output"))
    )
    (net (code "70") (name "unconnected-(IC4A-Q5-Pad3)") (class "Default")
      (node (ref "IC4") (pin "3") (pinfunction "Q5_3") (pintype "output"))
    )
    (net (code "71") (name "unconnected-(IC4A-Q6-Pad2)") (class "Default")
      (node (ref "IC4") (pin "2") (pinfunction "Q6_2") (pintype "output"))
    )
    (net (code "72") (name "unconnected-(IC4A-Q7-Pad4)") (class "Default")
      (node (ref "IC4") (pin "4") (pinfunction "Q7_4") (pintype "output"))
    )
    (net (code "73") (name "unconnected-(IC4A-Q8-Pad13)") (class "Default")
      (node (ref "IC4") (pin "13") (pinfunction "Q8_13") (pintype "output"))
    )
    (net (code "74") (name "unconnected-(IC4A-Q9-Pad12)") (class "Default")
      (node (ref "IC4") (pin "12") (pinfunction "Q9_12") (pintype "output"))
    )
    (net (code "75") (name "unconnected-(IC4A-Q10-Pad14)") (class "Default")
      (node (ref "IC4") (pin "14") (pinfunction "Q10_14") (pintype "output"))
    )
    (net (code "76") (name "unconnected-(IC4A-Q11-Pad15)") (class "Default")
      (node (ref "IC4") (pin "15") (pinfunction "Q11_15") (pintype "output"))
    )
    (net (code "77") (name "unconnected-(IC4A-Q12-Pad1)") (class "Default")
      (node (ref "IC4") (pin "1") (pinfunction "Q12_1") (pintype "output"))
    )
    (net (code "78") (name "unconnected-(JP7-Pad16)") (class "Default")
      (node (ref "JP7") (pin "16") (pinfunction "16_16") (pintype "passive"))
    )
    (net (code "79") (name "unconnected-(M1-D0{slash}RX-PadJ7.11)") (class "Default")
      (node (ref "M1") (pin "J7.11") (pinfunction "D0/RX_J7.11") (pintype "bidirectional"))
    )
    (net (code "80") (name "unconnected-(M1-D1{slash}TX-PadJ7.12)") (class "Default")
      (node (ref "M1") (pin "J7.12") (pinfunction "D1/TX_J7.12") (pintype "bidirectional"))
    )
    (net (code "81") (name "unconnected-(M1-D11-PadJ6.11)") (class "Default")
      (node (ref "M1") (pin "J6.11") (pinfunction "D11_J6.11") (pintype "bidirectional"))
    )
    (net (code "82") (name "unconnected-(M1-RST.1-PadJ6.3)") (class "Default")
      (node (ref "M1") (pin "J6.3") (pinfunction "RST.1_J6.3") (pintype "bidirectional"))
    )
    (net (code "83") (name "unconnected-(M1-RST.2-PadJ7.10)") (class "Default")
      (node (ref "M1") (pin "J7.10") (pinfunction "RST.2_J7.10") (pintype "bidirectional"))
    )
  )
)
